# H18R10.net
KiCad netlist of a schematic drawn in EAGLE
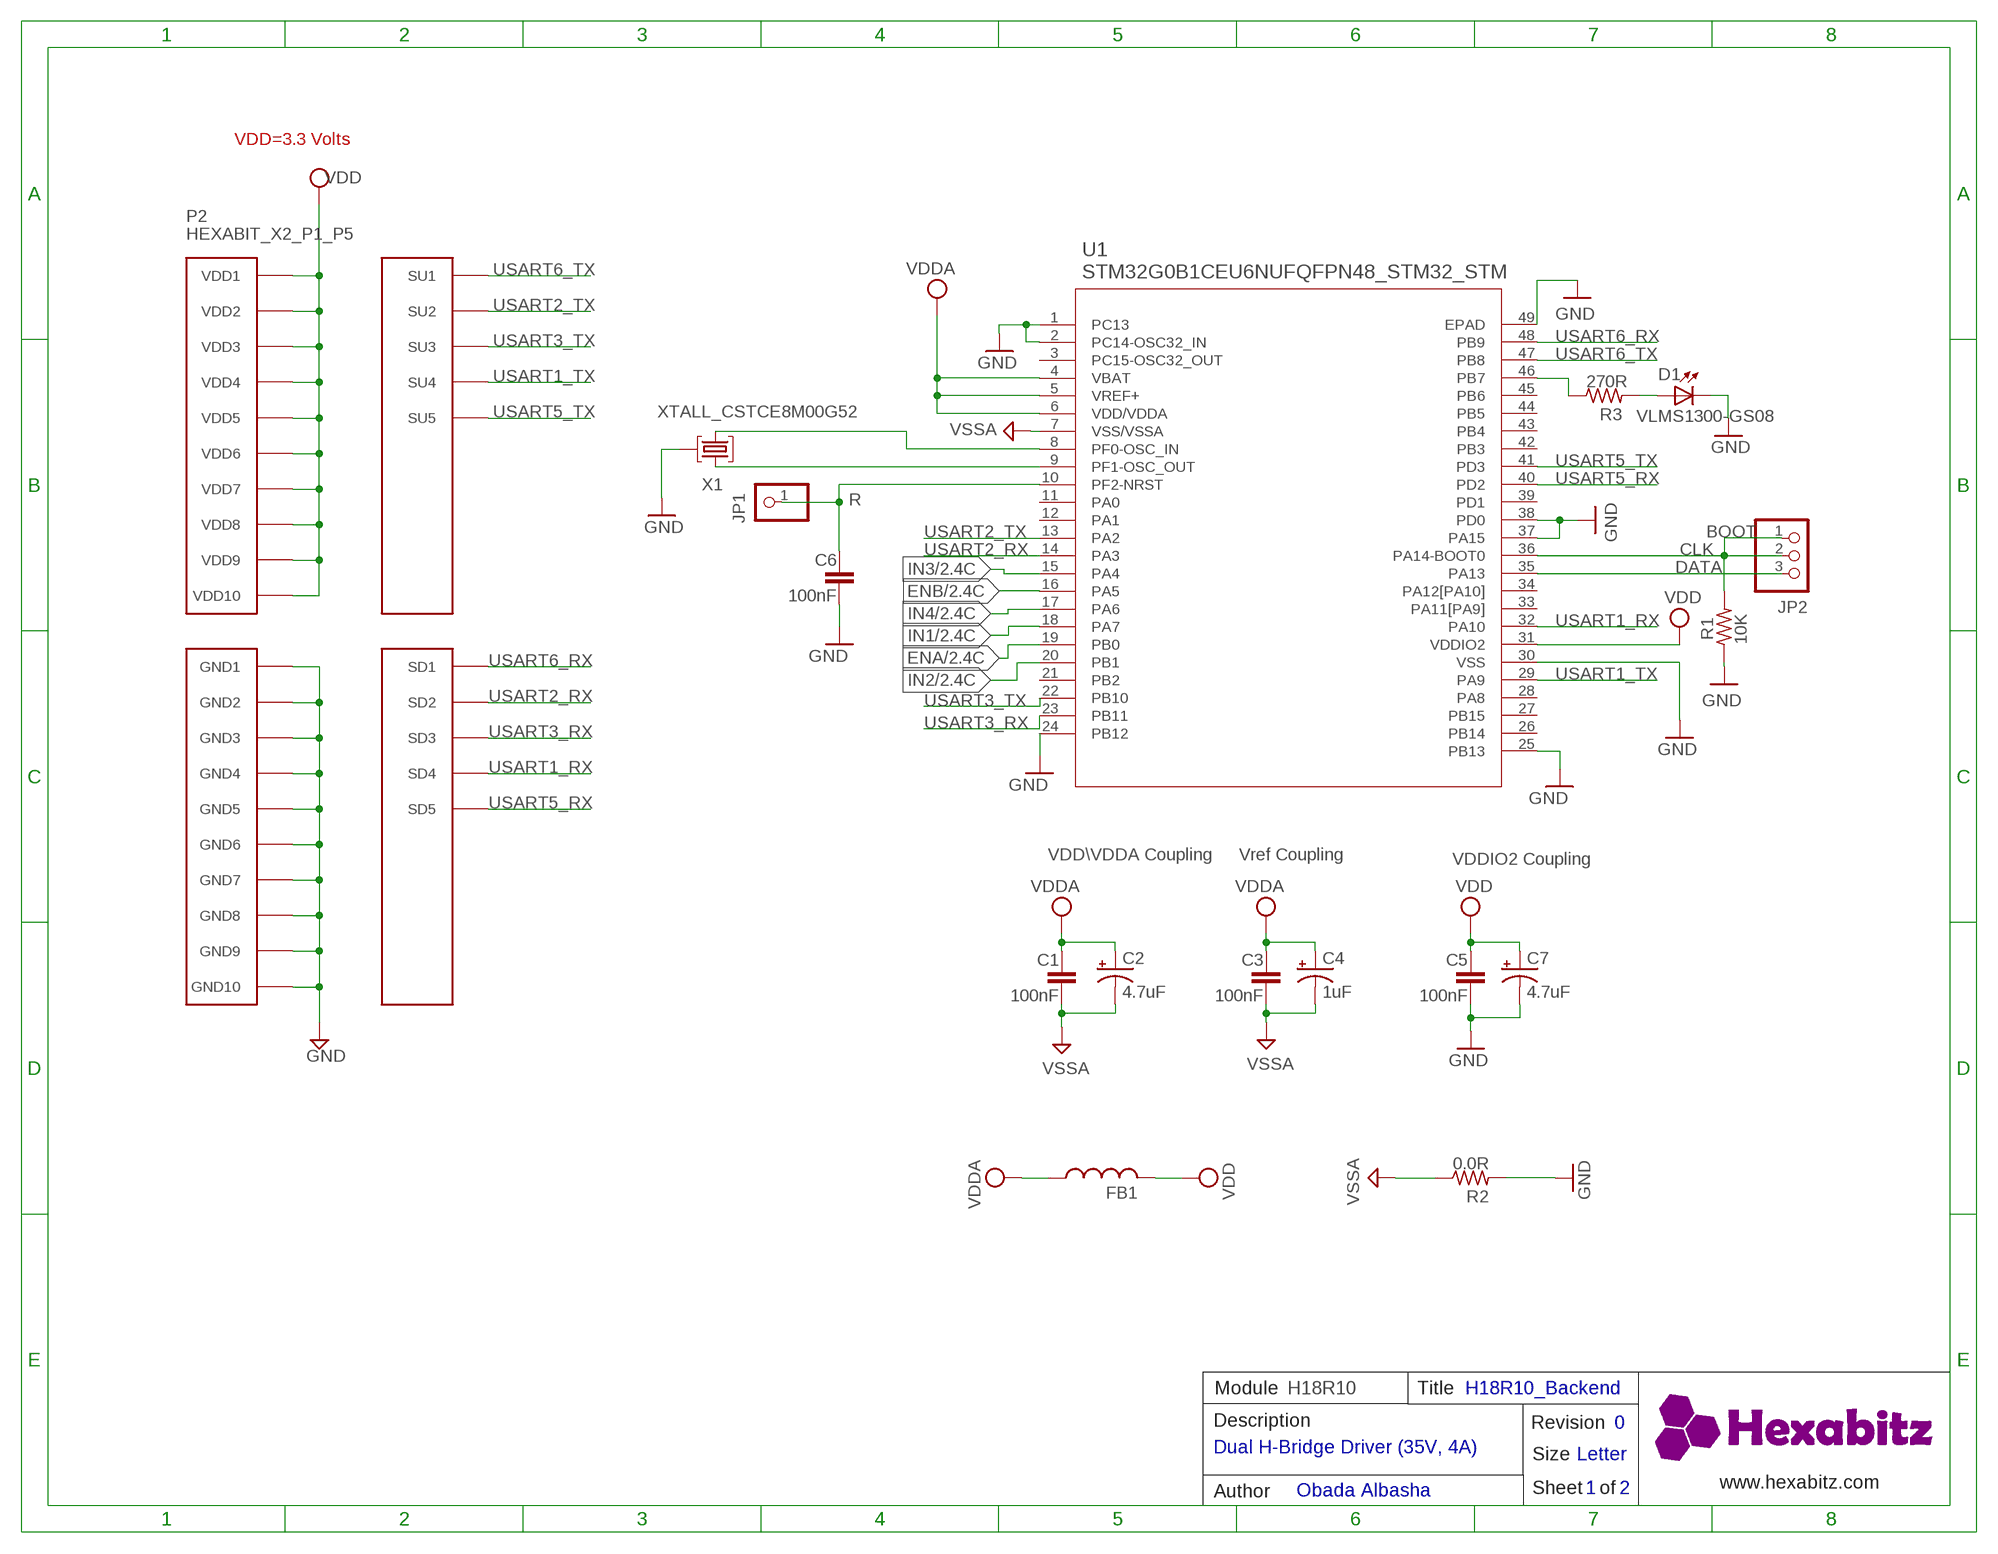
[diagram p0: schematic, sheet 1]
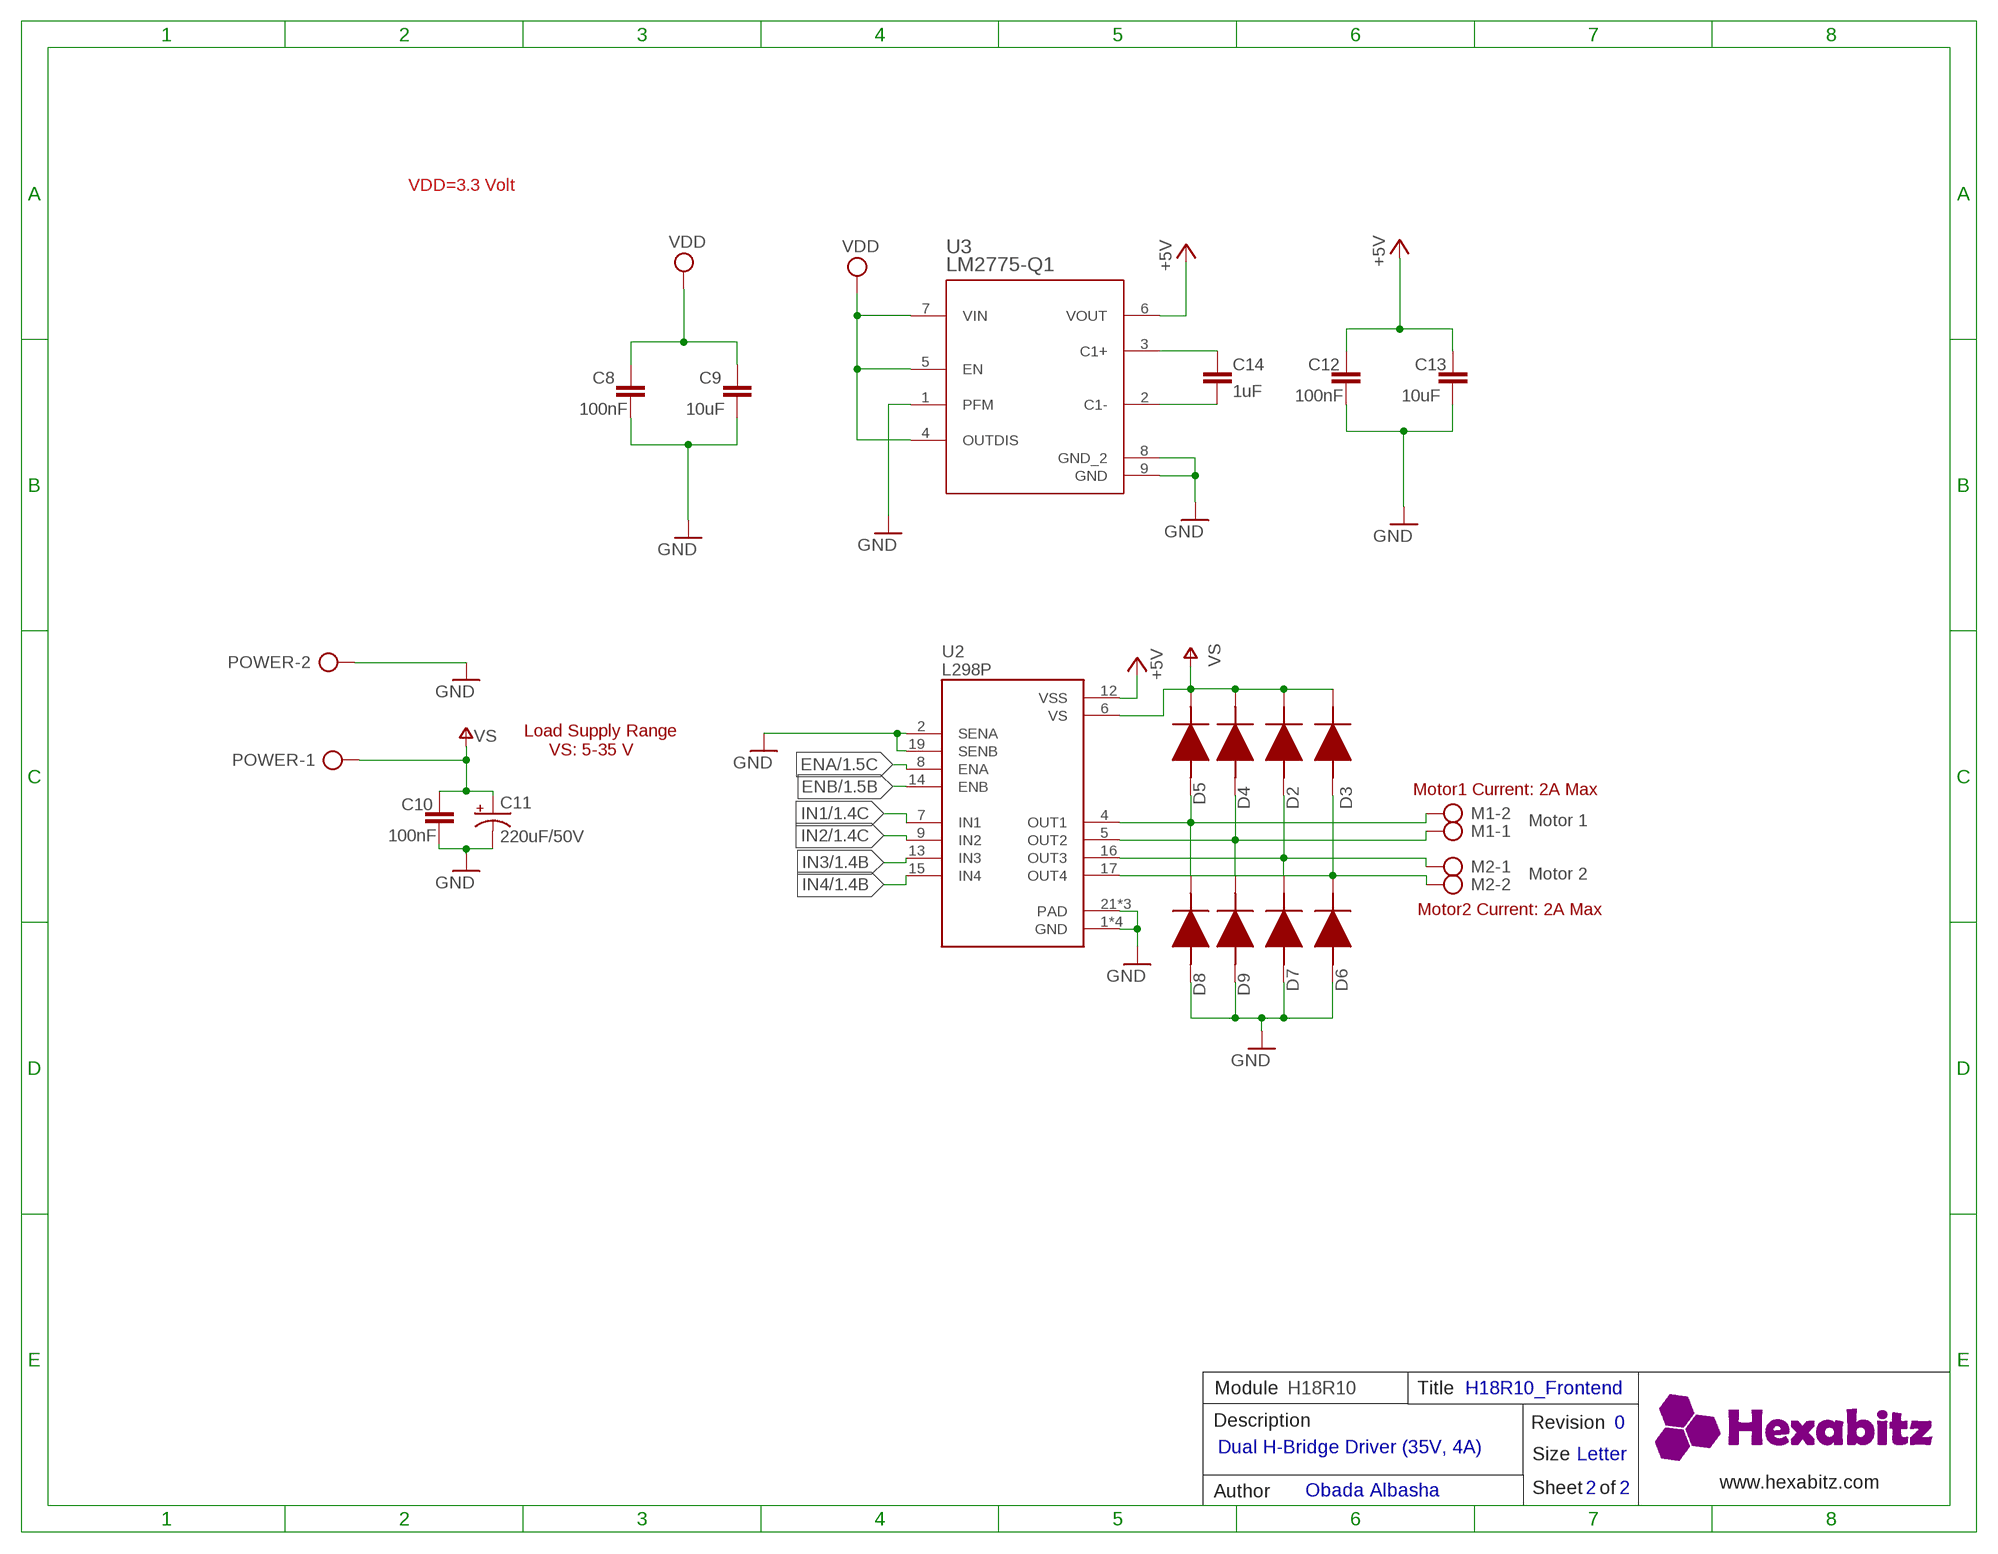
[diagram p1: schematic, sheet 2]

(export (version "E")
  (design (tool "Eeschema 10.0.6"))
  (components
    (comp (ref "C8")
      (value "100nF")
      (footprint "eagle-import:C-0603")
      (libsource (lib "eagle-import") (part "C-0603"))
    )
    (comp (ref "C9")
      (value "10uF")
      (footprint "eagle-import:C-0603")
      (libsource (lib "eagle-import") (part "C-0603"))
    )
    (comp (ref "C10")
      (value "100nF")
      (footprint "eagle-import:C-0603")
      (libsource (lib "eagle-import") (part "C-0603"))
    )
    (comp (ref "C11")
      (value "220uF/50V")
      (footprint "eagle-import:TT5D10")
      (libsource (lib "eagle-import") (part "CPOL-USTT5D10"))
    )
    (comp (ref "C12")
      (value "100nF")
      (footprint "eagle-import:C-0603")
      (libsource (lib "eagle-import") (part "C-0603"))
    )
    (comp (ref "C13")
      (value "10uF")
      (footprint "eagle-import:C-0603")
      (libsource (lib "eagle-import") (part "C-0603"))
    )
    (comp (ref "C14")
      (value "1uF")
      (footprint "eagle-import:C-0603")
      (libsource (lib "eagle-import") (part "C-0603"))
    )
    (comp (ref "D2")
      (value "MBR120ESFT1G")
      (footprint "eagle-import:SODFL3616X98N")
      (fields (field (name "ARROW_PART_NUMBER") "FSM17PL-TP"))
      (libsource (lib "eagle-import") (part "MBR120ESFT1G"))
    )
    (comp (ref "D3")
      (value "MBR120ESFT1G")
      (footprint "eagle-import:SODFL3616X98N")
      (fields (field (name "ARROW_PART_NUMBER") "FSM17PL-TP"))
      (libsource (lib "eagle-import") (part "MBR120ESFT1G"))
    )
    (comp (ref "D4")
      (value "MBR120ESFT1G")
      (footprint "eagle-import:SODFL3616X98N")
      (fields (field (name "ARROW_PART_NUMBER") "FSM17PL-TP"))
      (libsource (lib "eagle-import") (part "MBR120ESFT1G"))
    )
    (comp (ref "D5")
      (value "MBR120ESFT1G")
      (footprint "eagle-import:SODFL3616X98N")
      (fields (field (name "ARROW_PART_NUMBER") "FSM17PL-TP"))
      (libsource (lib "eagle-import") (part "MBR120ESFT1G"))
    )
    (comp (ref "D6")
      (value "MBR120ESFT1G")
      (footprint "eagle-import:SODFL3616X98N")
      (fields (field (name "ARROW_PART_NUMBER") "FSM17PL-TP"))
      (libsource (lib "eagle-import") (part "MBR120ESFT1G"))
    )
    (comp (ref "D7")
      (value "MBR120ESFT1G")
      (footprint "eagle-import:SODFL3616X98N")
      (fields (field (name "ARROW_PART_NUMBER") "FSM17PL-TP"))
      (libsource (lib "eagle-import") (part "MBR120ESFT1G"))
    )
    (comp (ref "D8")
      (value "MBR120ESFT1G")
      (footprint "eagle-import:SODFL3616X98N")
      (fields (field (name "ARROW_PART_NUMBER") "FSM17PL-TP"))
      (libsource (lib "eagle-import") (part "MBR120ESFT1G"))
    )
    (comp (ref "D9")
      (value "MBR120ESFT1G")
      (footprint "eagle-import:SODFL3616X98N")
      (fields (field (name "ARROW_PART_NUMBER") "FSM17PL-TP"))
      (libsource (lib "eagle-import") (part "MBR120ESFT1G"))
    )
    (comp (ref "M1")
      (value "AK500/2")
      (footprint "eagle-import:AK500_2")
      (fields (field (name "MPN") "282836-2"))
      (libsource (lib "eagle-import") (part "AK500/2"))
    )
    (comp (ref "M2")
      (value "AK500/2")
      (footprint "eagle-import:AK500_2")
      (fields (field (name "MPN") "282836-2"))
      (libsource (lib "eagle-import") (part "AK500/2"))
    )
    (comp (ref "POWER")
      (value "AK500/2")
      (footprint "eagle-import:AK500_2")
      (fields (field (name "MPN") "282836-2"))
      (libsource (lib "eagle-import") (part "AK500/2"))
    )
    (comp (ref "U2")
      (value "L298P")
      (footprint "eagle-import:SOIC127P1420X360-20N")
      (fields (field (name "MF") "STMicroelectronics"))
      (libsource (lib "eagle-import") (part "L298P"))
    )
    (comp (ref "U3")
      (value "LM2775-Q1")
      (footprint "eagle-import:DSG0008A")
      (fields (field (name "MANUFACTURER") "Texas Instruments") (field (name "MPN") "LM2775QDSGRQ1"))
      (libsource (lib "eagle-import") (part "LM2775QDSGRQ1"))
    )
    (comp (ref "C1")
      (value "100nF")
      (footprint "eagle-import:C-0603")
      (libsource (lib "eagle-import") (part "C-0603"))
    )
    (comp (ref "C2")
      (value "4.7uF")
      (footprint "eagle-import:C-0805-POL")
      (libsource (lib "eagle-import") (part "C-0805-POL"))
    )
    (comp (ref "C3")
      (value "100nF")
      (footprint "eagle-import:C-0603")
      (libsource (lib "eagle-import") (part "C-0603"))
    )
    (comp (ref "C4")
      (value "1uF")
      (footprint "eagle-import:C-0805-POL")
      (libsource (lib "eagle-import") (part "C-0805-POL"))
    )
    (comp (ref "C5")
      (value "100nF")
      (footprint "eagle-import:C-0603")
      (libsource (lib "eagle-import") (part "C-0603"))
    )
    (comp (ref "C6")
      (value "100nF")
      (footprint "eagle-import:C-0603")
      (libsource (lib "eagle-import") (part "C-0603"))
    )
    (comp (ref "C7")
      (value "4.7uF")
      (footprint "eagle-import:C-0805-POL")
      (libsource (lib "eagle-import") (part "C-0805-POL"))
    )
    (comp (ref "D1")
      (value "VLMS1300-GS08")
      (footprint "eagle-import:VLMS1300-GS08")
      (fields
        (field (name "MFN") "Vishay")
        (field (name "MPN") "VLMS1300-GS08")
        (field (name "OCTOPART_URL") "https://octopart.com/vlms1300-gs08-vishay-21709201?r=sp&s=_gcP4_q8T1SC6PJQPTQ9yA")
      )
      (libsource (lib "eagle-import") (part "VLMS1300-GS08"))
    )
    (comp (ref "FB1")
      (value "FB-0603")
      (footprint "eagle-import:FB-0603")
      (libsource (lib "eagle-import") (part "FB-0603"))
    )
    (comp (ref "JP1")
      (value "R")
      (footprint "eagle-import:1X01")
      (fields (field (name "MPN") "87227-1"))
      (libsource (lib "eagle-import") (part "PINHD-1X1"))
    )
    (comp (ref "JP2")
      (value "PINHD-1X3")
      (footprint "eagle-import:1X03")
      (libsource (lib "eagle-import") (part "PINHD-1X3"))
    )
    (comp (ref "P2")
      (value "HEXABIT_X2_P1_P5")
      (footprint "eagle-import:HEXABIT_17.32_X2_P1_P5")
      (libsource (lib "eagle-import") (part "HEXABIT_X2_P1_P5"))
    )
    (comp (ref "R1")
      (value "10K")
      (footprint "eagle-import:R-0603")
      (libsource (lib "eagle-import") (part "R-0603"))
    )
    (comp (ref "R2")
      (value "0.0R")
      (footprint "eagle-import:R-0603")
      (libsource (lib "eagle-import") (part "R-0603"))
    )
    (comp (ref "R3")
      (value "270R")
      (footprint "eagle-import:R-0603")
      (libsource (lib "eagle-import") (part "R-0603"))
    )
    (comp (ref "U1")
      (value "STM32G0B1CEU6NUFQFPN48_STM32_STM")
      (footprint "eagle-import:UFQFPN48_STM32_STM")
      (fields
        (field (name "MPN") "STM32G0B1CEU6N")
        (field (name "COPYRIGHT") "Copyright (C) 2022 Ultra Librarian. All rights reserved.")
      )
      (libsource (lib "eagle-import") (part "STM32G0B1CEU6NUFQFPN48_STM32_STM"))
    )
    (comp (ref "X1")
      (value "XTALL_CSTCE8M00G52")
      (footprint "eagle-import:XTALL_CSTCE8M00G52")
      (fields (field (name "MPN") "CSTCE8M00G52Z-R0"))
      (libsource (lib "eagle-import") (part "XTALL_CSTCE8M00G52"))
    )
  )
  (nets
    (net (code "1") (name "+5V") (class "Default")
      (node (ref "C12") (pin "1") (pinfunction "1_1") (pintype "passive"))
      (node (ref "C13") (pin "1") (pinfunction "1_1") (pintype "passive"))
      (node (ref "U2") (pin "12") (pinfunction "VSS_12") (pintype "power_in"))
      (node (ref "U3") (pin "6") (pinfunction "VOUT_6") (pintype "power_in"))
    )
    (net (code "2") (name "CLK") (class "Default")
      (node (ref "JP2") (pin "1") (pinfunction "1_1") (pintype "passive"))
      (node (ref "JP2") (pin "2") (pinfunction "2_2") (pintype "passive"))
      (node (ref "R1") (pin "2") (pinfunction "2_2") (pintype "passive"))
      (node (ref "U1") (pin "36") (pinfunction "PA14-BOOT0_36") (pintype "bidirectional"))
    )
    (net (code "3") (name "DATA") (class "Default")
      (node (ref "JP2") (pin "3") (pinfunction "3_3") (pintype "passive"))
      (node (ref "U1") (pin "35") (pinfunction "PA13_35") (pintype "bidirectional"))
    )
    (net (code "4") (name "ENA") (class "Default")
      (node (ref "U1") (pin "19") (pinfunction "PB0_19") (pintype "bidirectional"))
      (node (ref "U2") (pin "8") (pinfunction "ENA_8") (pintype "input"))
    )
    (net (code "5") (name "ENB") (class "Default")
      (node (ref "U1") (pin "16") (pinfunction "PA5_16") (pintype "bidirectional"))
      (node (ref "U2") (pin "14") (pinfunction "ENB_14") (pintype "input"))
    )
    (net (code "6") (name "GND") (class "Default")
      (node (ref "C10") (pin "2") (pinfunction "2_2") (pintype "passive"))
      (node (ref "C11") (pin "-") (pinfunction "-_-") (pintype "passive"))
      (node (ref "C12") (pin "2") (pinfunction "2_2") (pintype "passive"))
      (node (ref "C13") (pin "2") (pinfunction "2_2") (pintype "passive"))
      (node (ref "C5") (pin "2") (pinfunction "2_2") (pintype "passive"))
      (node (ref "C6") (pin "2") (pinfunction "2_2") (pintype "passive"))
      (node (ref "C7") (pin "2") (pinfunction "-_2") (pintype "passive"))
      (node (ref "C8") (pin "2") (pinfunction "2_2") (pintype "passive"))
      (node (ref "C9") (pin "2") (pinfunction "2_2") (pintype "passive"))
      (node (ref "D1") (pin "C") (pinfunction "C_C") (pintype "passive"))
      (node (ref "D6") (pin "2") (pinfunction "A_2") (pintype "bidirectional"))
      (node (ref "D7") (pin "2") (pinfunction "A_2") (pintype "bidirectional"))
      (node (ref "D8") (pin "2") (pinfunction "A_2") (pintype "bidirectional"))
      (node (ref "D9") (pin "2") (pinfunction "A_2") (pintype "bidirectional"))
      (node (ref "P2") (pin "PAD_PD11") (pinfunction "GND1_PAD_PD11") (pintype "power_in"))
      (node (ref "P2") (pin "PAD_PD12") (pinfunction "GND2_PAD_PD12") (pintype "power_in"))
      (node (ref "P2") (pin "PAD_PD13") (pinfunction "GND3_PAD_PD13") (pintype "power_in"))
      (node (ref "P2") (pin "PAD_PD14") (pinfunction "GND4_PAD_PD14") (pintype "power_in"))
      (node (ref "P2") (pin "PAD_PD15") (pinfunction "GND5_PAD_PD15") (pintype "power_in"))
      (node (ref "P2") (pin "PAD_PD16") (pinfunction "GND6_PAD_PD16") (pintype "power_in"))
      (node (ref "P2") (pin "PAD_PD17") (pinfunction "GND7_PAD_PD17") (pintype "power_in"))
      (node (ref "P2") (pin "PAD_PD18") (pinfunction "GND8_PAD_PD18") (pintype "power_in"))
      (node (ref "P2") (pin "PAD_PD19") (pinfunction "GND9_PAD_PD19") (pintype "power_in"))
      (node (ref "P2") (pin "PAD_PD20") (pinfunction "GND10_PAD_PD20") (pintype "power_in"))
      (node (ref "POWER") (pin "2") (pinfunction "KL_2") (pintype "passive"))
      (node (ref "R1") (pin "1") (pinfunction "1_1") (pintype "passive"))
      (node (ref "R2") (pin "2") (pinfunction "2_2") (pintype "passive"))
      (node (ref "U1") (pin "1") (pinfunction "PC13_1") (pintype "bidirectional"))
      (node (ref "U1") (pin "2") (pinfunction "PC14-OSC32_IN_2") (pintype "bidirectional"))
      (node (ref "U1") (pin "24") (pinfunction "PB12_24") (pintype "bidirectional"))
      (node (ref "U1") (pin "25") (pinfunction "PB13_25") (pintype "bidirectional"))
      (node (ref "U1") (pin "30") (pinfunction "VSS_30") (pintype "passive"))
      (node (ref "U1") (pin "37") (pinfunction "PA15_37") (pintype "bidirectional"))
      (node (ref "U1") (pin "38") (pinfunction "PD0_38") (pintype "bidirectional"))
      (node (ref "U1") (pin "49") (pinfunction "EPAD_49") (pintype "passive"))
      (node (ref "U2") (pin "1") (pinfunction "GND_1") (pintype "passive"))
      (node (ref "U2") (pin "10") (pinfunction "GND_10") (pintype "passive"))
      (node (ref "U2") (pin "11") (pinfunction "GND_11") (pintype "passive"))
      (node (ref "U2") (pin "19") (pinfunction "SENB_19") (pintype "input"))
      (node (ref "U2") (pin "2") (pinfunction "SENA_2") (pintype "input"))
      (node (ref "U2") (pin "20") (pinfunction "GND_20") (pintype "passive"))
      (node (ref "U2") (pin "21") (pinfunction "PAD_21") (pintype "passive"))
      (node (ref "U2") (pin "22") (pinfunction "PAD_22") (pintype "passive"))
      (node (ref "U2") (pin "23") (pinfunction "PAD_23") (pintype "passive"))
      (node (ref "U3") (pin "1") (pinfunction "PFM_1") (pintype "input"))
      (node (ref "U3") (pin "8") (pinfunction "GND_2_8") (pintype "power_in"))
      (node (ref "U3") (pin "9") (pinfunction "GND_9") (pintype "power_in"))
      (node (ref "X1") (pin "P$2") (pinfunction "2_P$2") (pintype "passive"))
    )
    (net (code "7") (name "IN1") (class "Default")
      (node (ref "U1") (pin "18") (pinfunction "PA7_18") (pintype "bidirectional"))
      (node (ref "U2") (pin "7") (pinfunction "IN1_7") (pintype "input"))
    )
    (net (code "8") (name "IN2") (class "Default")
      (node (ref "U1") (pin "20") (pinfunction "PB1_20") (pintype "bidirectional"))
      (node (ref "U2") (pin "9") (pinfunction "IN2_9") (pintype "input"))
    )
    (net (code "9") (name "IN3") (class "Default")
      (node (ref "U1") (pin "15") (pinfunction "PA4_15") (pintype "bidirectional"))
      (node (ref "U2") (pin "13") (pinfunction "IN3_13") (pintype "input"))
    )
    (net (code "10") (name "IN4") (class "Default")
      (node (ref "U1") (pin "17") (pinfunction "PA6_17") (pintype "bidirectional"))
      (node (ref "U2") (pin "15") (pinfunction "IN4_15") (pintype "input"))
    )
    (net (code "11") (name "Net-(D1-PadA)") (class "Default")
      (node (ref "D1") (pin "A") (pinfunction "A_A") (pintype "passive"))
      (node (ref "R3") (pin "2") (pinfunction "2_2") (pintype "passive"))
    )
    (net (code "12") (name "Net-(D2-A)") (class "Default")
      (node (ref "D2") (pin "2") (pinfunction "A_2") (pintype "bidirectional"))
      (node (ref "D7") (pin "1") (pinfunction "K_1") (pintype "bidirectional"))
      (node (ref "M2") (pin "1") (pinfunction "KL_1") (pintype "passive"))
      (node (ref "U2") (pin "16") (pinfunction "OUT3_16") (pintype "output"))
    )
    (net (code "13") (name "Net-(D3-A)") (class "Default")
      (node (ref "D3") (pin "2") (pinfunction "A_2") (pintype "bidirectional"))
      (node (ref "D6") (pin "1") (pinfunction "K_1") (pintype "bidirectional"))
      (node (ref "M2") (pin "2") (pinfunction "KL_2") (pintype "passive"))
      (node (ref "U2") (pin "17") (pinfunction "OUT4_17") (pintype "output"))
    )
    (net (code "14") (name "Net-(D4-A)") (class "Default")
      (node (ref "D4") (pin "2") (pinfunction "A_2") (pintype "bidirectional"))
      (node (ref "D9") (pin "1") (pinfunction "K_1") (pintype "bidirectional"))
      (node (ref "M1") (pin "1") (pinfunction "KL_1") (pintype "passive"))
      (node (ref "U2") (pin "5") (pinfunction "OUT2_5") (pintype "output"))
    )
    (net (code "15") (name "Net-(D5-A)") (class "Default")
      (node (ref "D5") (pin "2") (pinfunction "A_2") (pintype "bidirectional"))
      (node (ref "D8") (pin "1") (pinfunction "K_1") (pintype "bidirectional"))
      (node (ref "M1") (pin "2") (pinfunction "KL_2") (pintype "passive"))
      (node (ref "U2") (pin "4") (pinfunction "OUT1_4") (pintype "output"))
    )
    (net (code "16") (name "Net-(U1-PB7)") (class "Default")
      (node (ref "R3") (pin "1") (pinfunction "1_1") (pintype "passive"))
      (node (ref "U1") (pin "46") (pinfunction "PB7_46") (pintype "bidirectional"))
    )
    (net (code "17") (name "Net-(U1-PF0-OSC_IN)") (class "Default")
      (node (ref "U1") (pin "8") (pinfunction "PF0-OSC_IN_8") (pintype "bidirectional"))
      (node (ref "X1") (pin "P$3") (pinfunction "3_P$3") (pintype "passive"))
    )
    (net (code "18") (name "Net-(U1-PF1-OSC_OUT)") (class "Default")
      (node (ref "U1") (pin "9") (pinfunction "PF1-OSC_OUT_9") (pintype "bidirectional"))
      (node (ref "X1") (pin "P$1") (pinfunction "1_P$1") (pintype "passive"))
    )
    (net (code "19") (name "Net-(U1-PF2-NRST)") (class "Default")
      (node (ref "C6") (pin "1") (pinfunction "1_1") (pintype "passive"))
      (node (ref "JP1") (pin "1") (pinfunction "1_1") (pintype "passive"))
      (node (ref "U1") (pin "10") (pinfunction "PF2-NRST_10") (pintype "bidirectional"))
    )
    (net (code "20") (name "Net-(U3-C1+)") (class "Default")
      (node (ref "C14") (pin "1") (pinfunction "1_1") (pintype "passive"))
      (node (ref "U3") (pin "3") (pinfunction "C1+_3") (pintype "power_in"))
    )
    (net (code "21") (name "Net-(U3-C1-)") (class "Default")
      (node (ref "C14") (pin "2") (pinfunction "2_2") (pintype "passive"))
      (node (ref "U3") (pin "2") (pinfunction "C1-_2") (pintype "power_in"))
    )
    (net (code "22") (name "USART1_RX") (class "Default")
      (node (ref "P2") (pin "PAD_PD4") (pinfunction "SD4_PAD_PD4") (pintype "bidirectional"))
      (node (ref "U1") (pin "32") (pinfunction "PA10_32") (pintype "bidirectional"))
    )
    (net (code "23") (name "USART1_TX") (class "Default")
      (node (ref "P2") (pin "PAD_PU4") (pinfunction "SU4_PAD_PU4") (pintype "bidirectional"))
      (node (ref "U1") (pin "29") (pinfunction "PA9_29") (pintype "bidirectional"))
    )
    (net (code "24") (name "USART2_RX") (class "Default")
      (node (ref "P2") (pin "PAD_PD2") (pinfunction "SD2_PAD_PD2") (pintype "bidirectional"))
      (node (ref "U1") (pin "14") (pinfunction "PA3_14") (pintype "bidirectional"))
    )
    (net (code "25") (name "USART2_TX") (class "Default")
      (node (ref "P2") (pin "PAD_PU2") (pinfunction "SU2_PAD_PU2") (pintype "bidirectional"))
      (node (ref "U1") (pin "13") (pinfunction "PA2_13") (pintype "bidirectional"))
    )
    (net (code "26") (name "USART3_RX") (class "Default")
      (node (ref "P2") (pin "PAD_PD3") (pinfunction "SD3_PAD_PD3") (pintype "bidirectional"))
      (node (ref "U1") (pin "23") (pinfunction "PB11_23") (pintype "bidirectional"))
    )
    (net (code "27") (name "USART3_TX") (class "Default")
      (node (ref "P2") (pin "PAD_PU3") (pinfunction "SU3_PAD_PU3") (pintype "bidirectional"))
      (node (ref "U1") (pin "22") (pinfunction "PB10_22") (pintype "bidirectional"))
    )
    (net (code "28") (name "USART5_RX") (class "Default")
      (node (ref "P2") (pin "PAD_PD5") (pinfunction "SD5_PAD_PD5") (pintype "bidirectional"))
      (node (ref "U1") (pin "40") (pinfunction "PD2_40") (pintype "bidirectional"))
    )
    (net (code "29") (name "USART5_TX") (class "Default")
      (node (ref "P2") (pin "PAD_PU5") (pinfunction "SU5_PAD_PU5") (pintype "bidirectional"))
      (node (ref "U1") (pin "41") (pinfunction "PD3_41") (pintype "bidirectional"))
    )
    (net (code "30") (name "USART6_RX") (class "Default")
      (node (ref "P2") (pin "PAD_PD1") (pinfunction "SD1_PAD_PD1") (pintype "bidirectional"))
      (node (ref "U1") (pin "48") (pinfunction "PB9_48") (pintype "bidirectional"))
    )
    (net (code "31") (name "USART6_TX") (class "Default")
      (node (ref "P2") (pin "PAD_PU1") (pinfunction "SU1_PAD_PU1") (pintype "bidirectional"))
      (node (ref "U1") (pin "47") (pinfunction "PB8_47") (pintype "bidirectional"))
    )
    (net (code "32") (name "V+") (class "Default")
      (node (ref "C10") (pin "1") (pinfunction "1_1") (pintype "passive"))
      (node (ref "C11") (pin "+") (pinfunction "+_+") (pintype "passive"))
      (node (ref "D2") (pin "1") (pinfunction "K_1") (pintype "bidirectional"))
      (node (ref "D3") (pin "1") (pinfunction "K_1") (pintype "bidirectional"))
      (node (ref "D4") (pin "1") (pinfunction "K_1") (pintype "bidirectional"))
      (node (ref "D5") (pin "1") (pinfunction "K_1") (pintype "bidirectional"))
      (node (ref "POWER") (pin "1") (pinfunction "KL_1") (pintype "passive"))
      (node (ref "U2") (pin "6") (pinfunction "VS_6") (pintype "power_in"))
    )
    (net (code "33") (name "VDD") (class "Default")
      (node (ref "C5") (pin "1") (pinfunction "1_1") (pintype "passive"))
      (node (ref "C7") (pin "1") (pinfunction "+_1") (pintype "passive"))
      (node (ref "C8") (pin "1") (pinfunction "1_1") (pintype "passive"))
      (node (ref "C9") (pin "1") (pinfunction "1_1") (pintype "passive"))
      (node (ref "FB1") (pin "2") (pinfunction "2_2") (pintype "passive"))
      (node (ref "P2") (pin "PAD_PU11") (pinfunction "VDD1_PAD_PU11") (pintype "power_in"))
      (node (ref "P2") (pin "PAD_PU12") (pinfunction "VDD2_PAD_PU12") (pintype "power_in"))
      (node (ref "P2") (pin "PAD_PU13") (pinfunction "VDD3_PAD_PU13") (pintype "power_in"))
      (node (ref "P2") (pin "PAD_PU14") (pinfunction "VDD4_PAD_PU14") (pintype "power_in"))
      (node (ref "P2") (pin "PAD_PU15") (pinfunction "VDD5_PAD_PU15") (pintype "power_in"))
      (node (ref "P2") (pin "PAD_PU16") (pinfunction "VDD6_PAD_PU16") (pintype "power_in"))
      (node (ref "P2") (pin "PAD_PU17") (pinfunction "VDD7_PAD_PU17") (pintype "power_in"))
      (node (ref "P2") (pin "PAD_PU18") (pinfunction "VDD8_PAD_PU18") (pintype "power_in"))
      (node (ref "P2") (pin "PAD_PU19") (pinfunction "VDD9_PAD_PU19") (pintype "power_in"))
      (node (ref "P2") (pin "PAD_PU20") (pinfunction "VDD10_PAD_PU20") (pintype "power_in"))
      (node (ref "U1") (pin "31") (pinfunction "VDDIO2_31") (pintype "power_in"))
      (node (ref "U3") (pin "4") (pinfunction "OUTDIS_4") (pintype "input"))
      (node (ref "U3") (pin "5") (pinfunction "EN_5") (pintype "input"))
      (node (ref "U3") (pin "7") (pinfunction "VIN_7") (pintype "power_in"))
    )
    (net (code "34") (name "VDDA") (class "Default")
      (node (ref "C1") (pin "1") (pinfunction "1_1") (pintype "passive"))
      (node (ref "C2") (pin "1") (pinfunction "+_1") (pintype "passive"))
      (node (ref "C3") (pin "1") (pinfunction "1_1") (pintype "passive"))
      (node (ref "C4") (pin "1") (pinfunction "+_1") (pintype "passive"))
      (node (ref "FB1") (pin "1") (pinfunction "1_1") (pintype "passive"))
      (node (ref "U1") (pin "4") (pinfunction "VBAT_4") (pintype "power_in"))
      (node (ref "U1") (pin "5") (pinfunction "VREF+_5") (pintype "power_in"))
      (node (ref "U1") (pin "6") (pinfunction "VDD/VDDA_6") (pintype "power_in"))
    )
    (net (code "35") (name "VSSA") (class "Default")
      (node (ref "C1") (pin "2") (pinfunction "2_2") (pintype "passive"))
      (node (ref "C2") (pin "2") (pinfunction "-_2") (pintype "passive"))
      (node (ref "C3") (pin "2") (pinfunction "2_2") (pintype "passive"))
      (node (ref "C4") (pin "2") (pinfunction "-_2") (pintype "passive"))
      (node (ref "R2") (pin "1") (pinfunction "1_1") (pintype "passive"))
      (node (ref "U1") (pin "7") (pinfunction "VSS/VSSA_7") (pintype "passive"))
    )
    (net (code "36") (name "unconnected-(U1-PA0-Pad11)") (class "Default")
      (node (ref "U1") (pin "11") (pinfunction "PA0_11") (pintype "bidirectional"))
    )
    (net (code "37") (name "unconnected-(U1-PA1-Pad12)") (class "Default")
      (node (ref "U1") (pin "12") (pinfunction "PA1_12") (pintype "bidirectional"))
    )
    (net (code "38") (name "unconnected-(U1-PA8-Pad28)") (class "Default")
      (node (ref "U1") (pin "28") (pinfunction "PA8_28") (pintype "bidirectional"))
    )
    (net (code "39") (name "unconnected-(U1-PA11[PA9]-Pad33)") (class "Default")
      (node (ref "U1") (pin "33") (pinfunction "PA11[PA9]_33") (pintype "bidirectional"))
    )
    (net (code "40") (name "unconnected-(U1-PA12[PA10]-Pad34)") (class "Default")
      (node (ref "U1") (pin "34") (pinfunction "PA12[PA10]_34") (pintype "bidirectional"))
    )
    (net (code "41") (name "unconnected-(U1-PB2-Pad21)") (class "Default")
      (node (ref "U1") (pin "21") (pinfunction "PB2_21") (pintype "bidirectional"))
    )
    (net (code "42") (name "unconnected-(U1-PB3-Pad42)") (class "Default")
      (node (ref "U1") (pin "42") (pinfunction "PB3_42") (pintype "bidirectional"))
    )
    (net (code "43") (name "unconnected-(U1-PB4-Pad43)") (class "Default")
      (node (ref "U1") (pin "43") (pinfunction "PB4_43") (pintype "bidirectional"))
    )
    (net (code "44") (name "unconnected-(U1-PB5-Pad44)") (class "Default")
      (node (ref "U1") (pin "44") (pinfunction "PB5_44") (pintype "bidirectional"))
    )
    (net (code "45") (name "unconnected-(U1-PB6-Pad45)") (class "Default")
      (node (ref "U1") (pin "45") (pinfunction "PB6_45") (pintype "bidirectional"))
    )
    (net (code "46") (name "unconnected-(U1-PB14-Pad26)") (class "Default")
      (node (ref "U1") (pin "26") (pinfunction "PB14_26") (pintype "bidirectional"))
    )
    (net (code "47") (name "unconnected-(U1-PB15-Pad27)") (class "Default")
      (node (ref "U1") (pin "27") (pinfunction "PB15_27") (pintype "bidirectional"))
    )
    (net (code "48") (name "unconnected-(U1-PC15-OSC32_OUT-Pad3)") (class "Default")
      (node (ref "U1") (pin "3") (pinfunction "PC15-OSC32_OUT_3") (pintype "bidirectional"))
    )
    (net (code "49") (name "unconnected-(U1-PD1-Pad39)") (class "Default")
      (node (ref "U1") (pin "39") (pinfunction "PD1_39") (pintype "bidirectional"))
    )
  )
)
